# charlieplate3.net
KiCad netlist of a schematic drawn in EAGLE
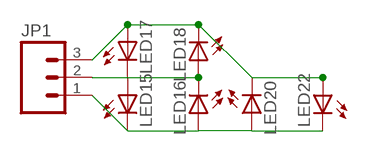
[diagram p0: schematic, sheet 1]

(export (version "E")
  (design (tool "Eeschema 10.0.6"))
  (components
    (comp (ref "JP1")
      (value "M03PTH")
      (footprint "eagle-import:1X03")
      (libsource (lib "eagle-import") (part "M03PTH"))
    )
    (comp (ref "LED15")
      (value "LED3MM")
      (footprint "eagle-import:LED3MM")
      (libsource (lib "eagle-import") (part "LED3MM"))
    )
    (comp (ref "LED16")
      (value "LED3MM")
      (footprint "eagle-import:LED3MM")
      (libsource (lib "eagle-import") (part "LED3MM"))
    )
    (comp (ref "LED17")
      (value "LED3MM")
      (footprint "eagle-import:LED3MM")
      (libsource (lib "eagle-import") (part "LED3MM"))
    )
    (comp (ref "LED18")
      (value "LED3MM")
      (footprint "eagle-import:LED3MM")
      (libsource (lib "eagle-import") (part "LED3MM"))
    )
    (comp (ref "LED20")
      (value "LED3MM")
      (footprint "eagle-import:LED3MM")
      (libsource (lib "eagle-import") (part "LED3MM"))
    )
    (comp (ref "LED22")
      (value "LED3MM")
      (footprint "eagle-import:LED3MM")
      (libsource (lib "eagle-import") (part "LED3MM"))
    )
  )
  (nets
    (net (code "1") (name "Net-(LED15-C)") (class "Default")
      (node (ref "JP1") (pin "1") (pinfunction "1_1") (pintype "passive"))
      (node (ref "LED15") (pin "K") (pinfunction "C_K") (pintype "passive"))
      (node (ref "LED16") (pin "A") (pinfunction "A_A") (pintype "passive"))
      (node (ref "LED20") (pin "A") (pinfunction "A_A") (pintype "passive"))
      (node (ref "LED22") (pin "K") (pinfunction "C_K") (pintype "passive"))
    )
    (net (code "2") (name "Net-(LED16-C)") (class "Default")
      (node (ref "JP1") (pin "2") (pinfunction "2_2") (pintype "passive"))
      (node (ref "LED15") (pin "A") (pinfunction "A_A") (pintype "passive"))
      (node (ref "LED16") (pin "K") (pinfunction "C_K") (pintype "passive"))
      (node (ref "LED17") (pin "K") (pinfunction "C_K") (pintype "passive"))
      (node (ref "LED18") (pin "A") (pinfunction "A_A") (pintype "passive"))
    )
    (net (code "3") (name "Net-(LED18-C)") (class "Default")
      (node (ref "JP1") (pin "3") (pinfunction "3_3") (pintype "passive"))
      (node (ref "LED17") (pin "A") (pinfunction "A_A") (pintype "passive"))
      (node (ref "LED18") (pin "K") (pinfunction "C_K") (pintype "passive"))
      (node (ref "LED20") (pin "K") (pinfunction "C_K") (pintype "passive"))
      (node (ref "LED22") (pin "A") (pinfunction "A_A") (pintype "passive"))
    )
  )
)
